# 09_-Digital-IO.net
KiCad netlist of a schematic drawn in Altium Designer
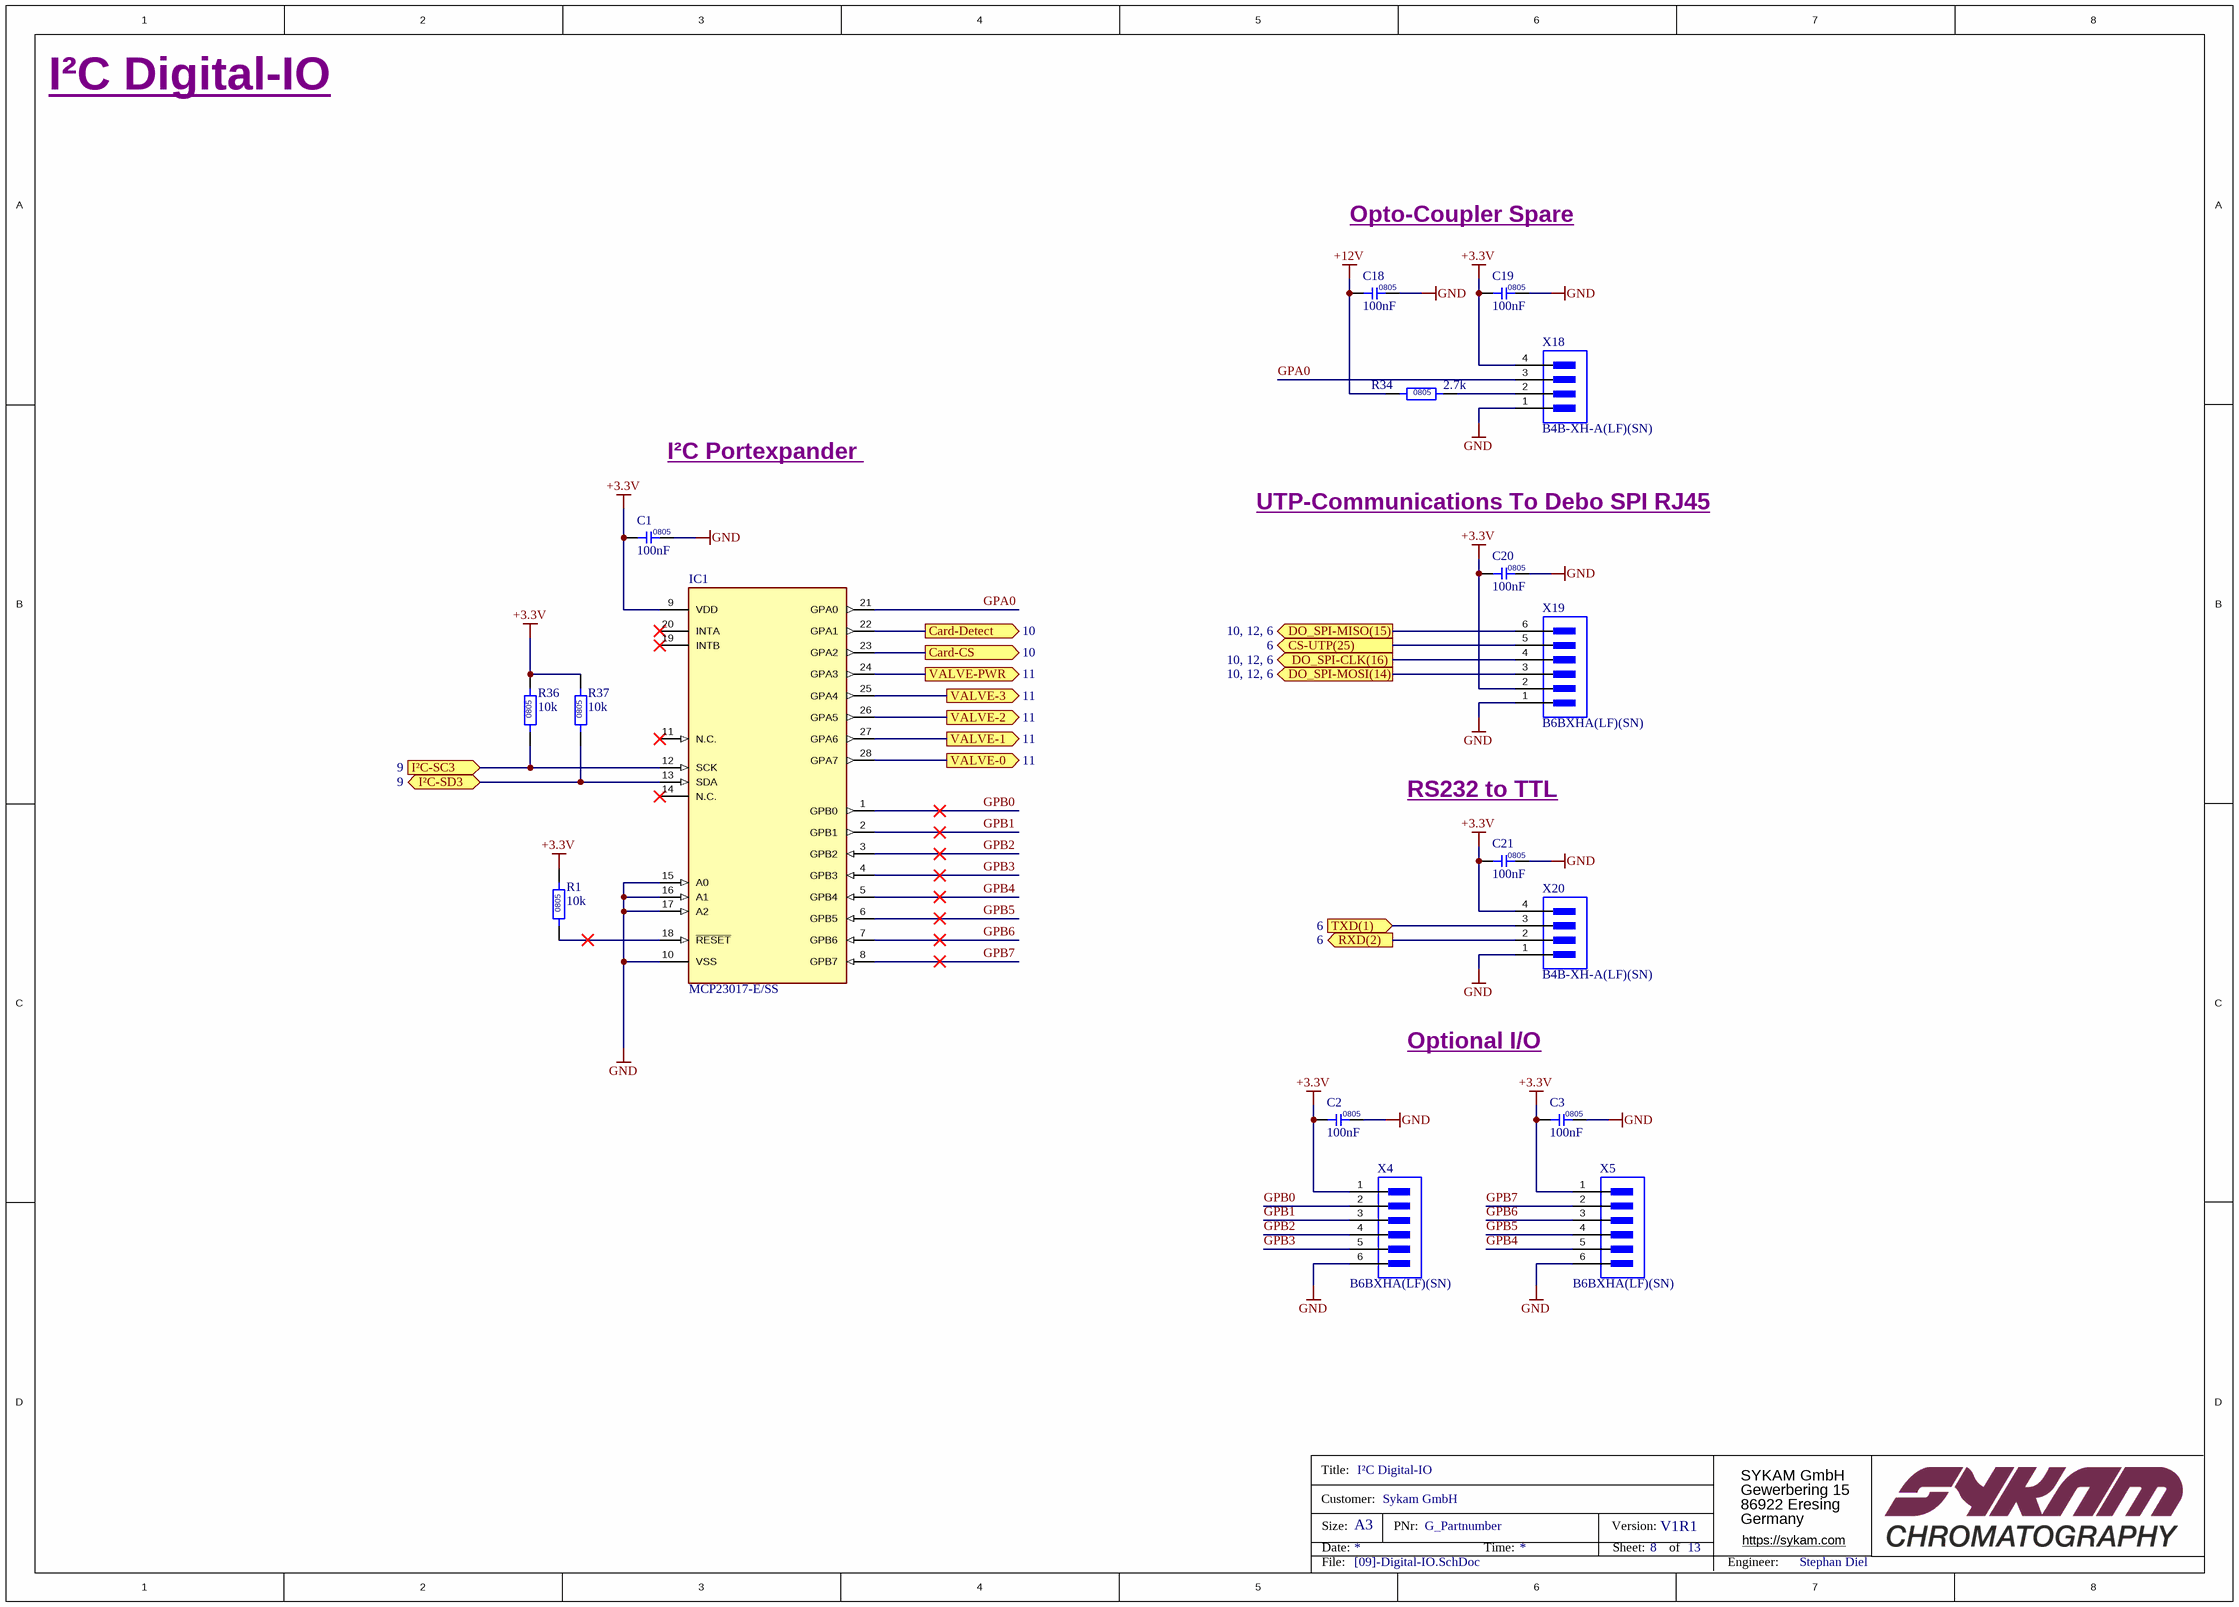
[diagram p0: [09]-Digital-IO.SchDoc]

(export (version "E")
  (design (tool "Eeschema 10.0.6"))
  (components
    (comp (ref "C1")
      (value "100nF")
      (footprint "C0805")
      (description "CAP CER 0.1UF 50V X7R 0805")
      (fields
        (field (name "MANUFACTURER PART NUMBER") "CC0805KRX7R9BB104")
        (field (name "TOLERANCE") "10%")
        (field (name "PCBCHECKED") "initials after Checked")
        (field (name "SCHCHECKED") "Initials after checked")
      )
      (libsource (lib "ToradexMainBoard-V0I1") (part "C_100nF_CC0805KRX7R9BB104"))
    )
    (comp (ref "C2")
      (value "100nF")
      (footprint "C0805")
      (description "CAP CER 0.1UF 50V X7R 0805")
      (fields
        (field (name "MANUFACTURER PART NUMBER") "CC0805KRX7R9BB104")
        (field (name "TOLERANCE") "10%")
        (field (name "PCBCHECKED") "initials after Checked")
        (field (name "SCHCHECKED") "Initials after checked")
      )
      (libsource (lib "ToradexMainBoard-V0I1") (part "C_100nF_CC0805KRX7R9BB104"))
    )
    (comp (ref "C3")
      (value "100nF")
      (footprint "C0805")
      (description "CAP CER 0.1UF 50V X7R 0805")
      (fields
        (field (name "MANUFACTURER PART NUMBER") "CC0805KRX7R9BB104")
        (field (name "TOLERANCE") "10%")
        (field (name "PCBCHECKED") "initials after Checked")
        (field (name "SCHCHECKED") "Initials after checked")
      )
      (libsource (lib "ToradexMainBoard-V0I1") (part "C_100nF_CC0805KRX7R9BB104"))
    )
    (comp (ref "C18")
      (value "100nF")
      (footprint "C0805")
      (description "CAP CER 0.1UF 50V X7R 0805")
      (fields
        (field (name "MANUFACTURER PART NUMBER") "CC0805KRX7R9BB104")
        (field (name "TOLERANCE") "10%")
        (field (name "PCBCHECKED") "initials after Checked")
        (field (name "SCHCHECKED") "Initials after checked")
      )
      (libsource (lib "ToradexMainBoard-V0I1") (part "C_100nF_CC0805KRX7R9BB104"))
    )
    (comp (ref "C19")
      (value "100nF")
      (footprint "C0805")
      (description "CAP CER 0.1UF 50V X7R 0805")
      (fields
        (field (name "MANUFACTURER PART NUMBER") "CC0805KRX7R9BB104")
        (field (name "TOLERANCE") "10%")
        (field (name "PCBCHECKED") "initials after Checked")
        (field (name "SCHCHECKED") "Initials after checked")
      )
      (libsource (lib "ToradexMainBoard-V0I1") (part "C_100nF_CC0805KRX7R9BB104"))
    )
    (comp (ref "C20")
      (value "100nF")
      (footprint "C0805")
      (description "CAP CER 0.1UF 50V X7R 0805")
      (fields
        (field (name "MANUFACTURER PART NUMBER") "CC0805KRX7R9BB104")
        (field (name "TOLERANCE") "10%")
        (field (name "PCBCHECKED") "initials after Checked")
        (field (name "SCHCHECKED") "Initials after checked")
      )
      (libsource (lib "ToradexMainBoard-V0I1") (part "C_100nF_CC0805KRX7R9BB104"))
    )
    (comp (ref "C21")
      (value "100nF")
      (footprint "C0805")
      (description "CAP CER 0.1UF 50V X7R 0805")
      (fields
        (field (name "MANUFACTURER PART NUMBER") "CC0805KRX7R9BB104")
        (field (name "TOLERANCE") "10%")
        (field (name "PCBCHECKED") "initials after Checked")
        (field (name "SCHCHECKED") "Initials after checked")
      )
      (libsource (lib "ToradexMainBoard-V0I1") (part "C_100nF_CC0805KRX7R9BB104"))
    )
    (comp (ref "IC1")
      (value "MCP23017-E/SS")
      (footprint "IC_MCP23017-E/SS_SSOP28")
      (description "I²C Bus IC Operating temperature: -40...+125 °C Power supply: 1.8...5.5 V Package: SSOP-20")
      (fields (field (name "MANUFACTURER") "Microchip"))
      (libsource (lib "ToradexMainBoard-V0I1") (part "IC_MCP23017-E/SS"))
    )
    (comp (ref "R1")
      (value "10k")
      (footprint "R0805")
      (description "RES SMD 10K OHM 1% 1/8W 0805")
      (fields
        (field (name "MANUFACTURER PART NUMBER") "RC0805FR-0710KL")
        (field (name "TOLERANCE") "1%")
        (field (name "PCBCHECKED") "initials after Checked")
        (field (name "SCHCHECKED") "Initials after checked")
      )
      (libsource (lib "ToradexMainBoard-V0I1") (part "R_10k_RC0805FR-0710KL"))
    )
    (comp (ref "R34")
      (value "2.7k")
      (footprint "R0805")
      (fields
        (field (name "MANUFACTURER") "Yageo")
        (field (name "MANUFACTURER PART NUMBER") "RT0805FRE072K7L")
        (field (name "TOLERANCE") "1%")
      )
      (libsource (lib "ToradexMainBoard-V0I1") (part "R_2.7k_RT0805FRE072K7L"))
    )
    (comp (ref "R36")
      (value "10k")
      (footprint "R0805")
      (description "RES SMD 10K OHM 1% 1/8W 0805")
      (fields
        (field (name "MANUFACTURER PART NUMBER") "RC0805FR-0710KL")
        (field (name "TOLERANCE") "1%")
        (field (name "PCBCHECKED") "initials after Checked")
        (field (name "SCHCHECKED") "Initials after checked")
      )
      (libsource (lib "ToradexMainBoard-V0I1") (part "R_10k_RC0805FR-0710KL"))
    )
    (comp (ref "R37")
      (value "10k")
      (footprint "R0805")
      (description "RES SMD 10K OHM 1% 1/8W 0805")
      (fields
        (field (name "MANUFACTURER PART NUMBER") "RC0805FR-0710KL")
        (field (name "TOLERANCE") "1%")
        (field (name "PCBCHECKED") "initials after Checked")
        (field (name "SCHCHECKED") "Initials after checked")
      )
      (libsource (lib "ToradexMainBoard-V0I1") (part "R_10k_RC0805FR-0710KL"))
    )
    (comp (ref "X4")
      (value "B6BXHA(LF)(SN)")
      (footprint "B6BXHA(LF)(SN)")
      (description "CONN HEADER VERT 6POS 2.5MM")
      (fields (field (name "MANUFACTURER") "JST"))
      (libsource (lib "ToradexMainBoard-V0I1") (part "CON_6pol_B6BXHA(LF)(SN)"))
    )
    (comp (ref "X5")
      (value "B6BXHA(LF)(SN)")
      (footprint "B6BXHA(LF)(SN)")
      (description "CONN HEADER VERT 6POS 2.5MM")
      (fields (field (name "MANUFACTURER") "JST"))
      (libsource (lib "ToradexMainBoard-V0I1") (part "CON_6pol_B6BXHA(LF)(SN)"))
    )
    (comp (ref "X18")
      (value "B4B-XH-A(LF)(SN)")
      (footprint "CON_B4B-XH-A(LF)(SN)")
      (fields (field (name "MANUFACTURER") "JST"))
      (libsource (lib "ToradexMainBoard-V0I1") (part "CON_4pol_B4B-XH-A(LF)(SN)"))
    )
    (comp (ref "X19")
      (value "B6BXHA(LF)(SN)")
      (footprint "B6BXHA(LF)(SN)")
      (description "CONN HEADER VERT 6POS 2.5MM")
      (fields (field (name "MANUFACTURER") "JST"))
      (libsource (lib "") (part "CON_6pol_B6BXHA(LF)(SN)_1"))
    )
    (comp (ref "X20")
      (value "B4B-XH-A(LF)(SN)")
      (footprint "CON_B4B-XH-A(LF)(SN)")
      (fields (field (name "MANUFACTURER") "JST"))
      (libsource (lib "ToradexMainBoard-V0I1") (part "CON_4pol_B4B-XH-A(LF)(SN)"))
    )
  )
  (nets
    (net (code "1") (name "+3.3V") (class "Default")
      (node (ref "C1") (pin "1") (pinfunction "1_1") (pintype "passive"))
      (node (ref "C19") (pin "1") (pinfunction "1_1") (pintype "passive"))
      (node (ref "C2") (pin "1") (pinfunction "1_1") (pintype "passive"))
      (node (ref "C20") (pin "1") (pinfunction "1_1") (pintype "passive"))
      (node (ref "C21") (pin "1") (pinfunction "1_1") (pintype "passive"))
      (node (ref "C3") (pin "1") (pinfunction "1_1") (pintype "passive"))
      (node (ref "IC1") (pin "9") (pinfunction "VDD_9") (pintype "power_in"))
      (node (ref "R1") (pin "2") (pinfunction "2_2") (pintype "passive"))
      (node (ref "R36") (pin "2") (pinfunction "2_2") (pintype "passive"))
      (node (ref "R37") (pin "2") (pinfunction "2_2") (pintype "passive"))
      (node (ref "X18") (pin "4") (pintype "passive"))
      (node (ref "X19") (pin "2") (pintype "passive"))
      (node (ref "X20") (pin "4") (pintype "passive"))
      (node (ref "X4") (pin "1") (pintype "passive"))
      (node (ref "X5") (pin "1") (pintype "passive"))
    )
    (net (code "2") (name "+12V") (class "Default")
      (node (ref "C18") (pin "1") (pinfunction "1_1") (pintype "passive"))
      (node (ref "R34") (pin "1") (pinfunction "1_1") (pintype "passive"))
    )
    (net (code "3") (name "/CS-UTP(25)") (class "Default") (node (ref "X19") (pin "5") (pintype "passive")))
    (net (code "4") (name "/Card-CS") (class "Default")
      (node (ref "IC1") (pin "23") (pinfunction "GPA2_23") (pintype "output"))
    )
    (net (code "5") (name "/Card-Detect") (class "Default")
      (node (ref "IC1") (pin "22") (pinfunction "GPA1_22") (pintype "output"))
    )
    (net (code "6") (name "/DO_SPI-CLK(16)") (class "Default")
      (node (ref "X19") (pin "4") (pintype "passive"))
    )
    (net (code "7") (name "/DO_SPI-MISO(15)") (class "Default")
      (node (ref "X19") (pin "6") (pintype "passive"))
    )
    (net (code "8") (name "/DO_SPI-MOSI(14)") (class "Default")
      (node (ref "X19") (pin "3") (pintype "passive"))
    )
    (net (code "9") (name "/GPA0") (class "Default")
      (node (ref "IC1") (pin "21") (pinfunction "GPA0_21") (pintype "output"))
      (node (ref "X18") (pin "3") (pintype "passive"))
    )
    (net (code "10") (name "/GPB0") (class "Default")
      (node (ref "IC1") (pin "1") (pinfunction "GPB0_1") (pintype "output"))
      (node (ref "X4") (pin "2") (pintype "passive"))
    )
    (net (code "11") (name "/GPB1") (class "Default")
      (node (ref "IC1") (pin "2") (pinfunction "GPB1_2") (pintype "output"))
      (node (ref "X4") (pin "3") (pintype "passive"))
    )
    (net (code "12") (name "/GPB2") (class "Default")
      (node (ref "IC1") (pin "3") (pinfunction "GPB2_3") (pintype "input"))
      (node (ref "X4") (pin "4") (pintype "passive"))
    )
    (net (code "13") (name "/GPB3") (class "Default")
      (node (ref "IC1") (pin "4") (pinfunction "GPB3_4") (pintype "input"))
      (node (ref "X4") (pin "5") (pintype "passive"))
    )
    (net (code "14") (name "/GPB4") (class "Default")
      (node (ref "IC1") (pin "5") (pinfunction "GPB4_5") (pintype "input"))
      (node (ref "X5") (pin "5") (pintype "passive"))
    )
    (net (code "15") (name "/GPB5") (class "Default")
      (node (ref "IC1") (pin "6") (pinfunction "GPB5_6") (pintype "input"))
      (node (ref "X5") (pin "4") (pintype "passive"))
    )
    (net (code "16") (name "/GPB6") (class "Default")
      (node (ref "IC1") (pin "7") (pinfunction "GPB6_7") (pintype "input"))
      (node (ref "X5") (pin "3") (pintype "passive"))
    )
    (net (code "17") (name "/GPB7") (class "Default")
      (node (ref "IC1") (pin "8") (pinfunction "GPB7_8") (pintype "input"))
      (node (ref "X5") (pin "2") (pintype "passive"))
    )
    (net (code "18") (name "/I²C-SC3") (class "Default")
      (node (ref "IC1") (pin "12") (pinfunction "SCK_12") (pintype "input"))
      (node (ref "R36") (pin "1") (pinfunction "1_1") (pintype "passive"))
    )
    (net (code "19") (name "/I²C-SD3") (class "Default")
      (node (ref "IC1") (pin "13") (pinfunction "SDA_13") (pintype "input"))
      (node (ref "R37") (pin "1") (pinfunction "1_1") (pintype "passive"))
    )
    (net (code "20") (name "/RXD(2)") (class "Default") (node (ref "X20") (pin "2") (pintype "passive")))
    (net (code "21") (name "/TXD(1)") (class "Default") (node (ref "X20") (pin "3") (pintype "passive")))
    (net (code "22") (name "/VALVE-0") (class "Default")
      (node (ref "IC1") (pin "28") (pinfunction "GPA7_28") (pintype "output"))
    )
    (net (code "23") (name "/VALVE-1") (class "Default")
      (node (ref "IC1") (pin "27") (pinfunction "GPA6_27") (pintype "output"))
    )
    (net (code "24") (name "/VALVE-2") (class "Default")
      (node (ref "IC1") (pin "26") (pinfunction "GPA5_26") (pintype "output"))
    )
    (net (code "25") (name "/VALVE-3") (class "Default")
      (node (ref "IC1") (pin "25") (pinfunction "GPA4_25") (pintype "output"))
    )
    (net (code "26") (name "/VALVE-PWR") (class "Default")
      (node (ref "IC1") (pin "24") (pinfunction "GPA3_24") (pintype "output"))
    )
    (net (code "27") (name "GND") (class "Default")
      (node (ref "C1") (pin "2") (pinfunction "2_2") (pintype "passive"))
      (node (ref "C18") (pin "2") (pinfunction "2_2") (pintype "passive"))
      (node (ref "C19") (pin "2") (pinfunction "2_2") (pintype "passive"))
      (node (ref "C2") (pin "2") (pinfunction "2_2") (pintype "passive"))
      (node (ref "C20") (pin "2") (pinfunction "2_2") (pintype "passive"))
      (node (ref "C21") (pin "2") (pinfunction "2_2") (pintype "passive"))
      (node (ref "C3") (pin "2") (pinfunction "2_2") (pintype "passive"))
      (node (ref "IC1") (pin "10") (pinfunction "VSS_10") (pintype "power_in"))
      (node (ref "IC1") (pin "15") (pinfunction "A0_15") (pintype "input"))
      (node (ref "IC1") (pin "16") (pinfunction "A1_16") (pintype "input"))
      (node (ref "IC1") (pin "17") (pinfunction "A2_17") (pintype "input"))
      (node (ref "X18") (pin "1") (pintype "passive"))
      (node (ref "X19") (pin "1") (pintype "passive"))
      (node (ref "X20") (pin "1") (pintype "passive"))
      (node (ref "X4") (pin "6") (pintype "passive"))
      (node (ref "X5") (pin "6") (pintype "passive"))
    )
    (net (code "28") (name "Net-(IC1-~{RESET})") (class "Default")
      (node (ref "IC1") (pin "18") (pinfunction "~{RESET}_18") (pintype "input"))
      (node (ref "R1") (pin "1") (pinfunction "1_1") (pintype "passive"))
    )
    (net (code "29") (name "Net-(R34-Pad2)") (class "Default")
      (node (ref "R34") (pin "2") (pinfunction "2_2") (pintype "passive"))
      (node (ref "X18") (pin "2") (pintype "passive"))
    )
    (net (code "30") (name "unconnected-(IC1-INTA-Pad20)") (class "Default")
      (node (ref "IC1") (pin "20") (pinfunction "INTA_20") (pintype "open_collector+no_connect"))
    )
    (net (code "31") (name "unconnected-(IC1-INTB-Pad19)") (class "Default")
      (node (ref "IC1") (pin "19") (pinfunction "INTB_19") (pintype "open_collector+no_connect"))
    )
    (net (code "32") (name "unconnected-(IC1-N.C.-Pad11)") (class "Default")
      (node (ref "IC1") (pin "11") (pinfunction "N.C._11") (pintype "input+no_connect"))
    )
    (net (code "33") (name "unconnected-(IC1-N.C.-Pad14)") (class "Default")
      (node (ref "IC1") (pin "14") (pinfunction "N.C._14") (pintype "tri_state+no_connect"))
    )
  )
)
